# Control.net
KiCad netlist of a schematic drawn in Altium Designer
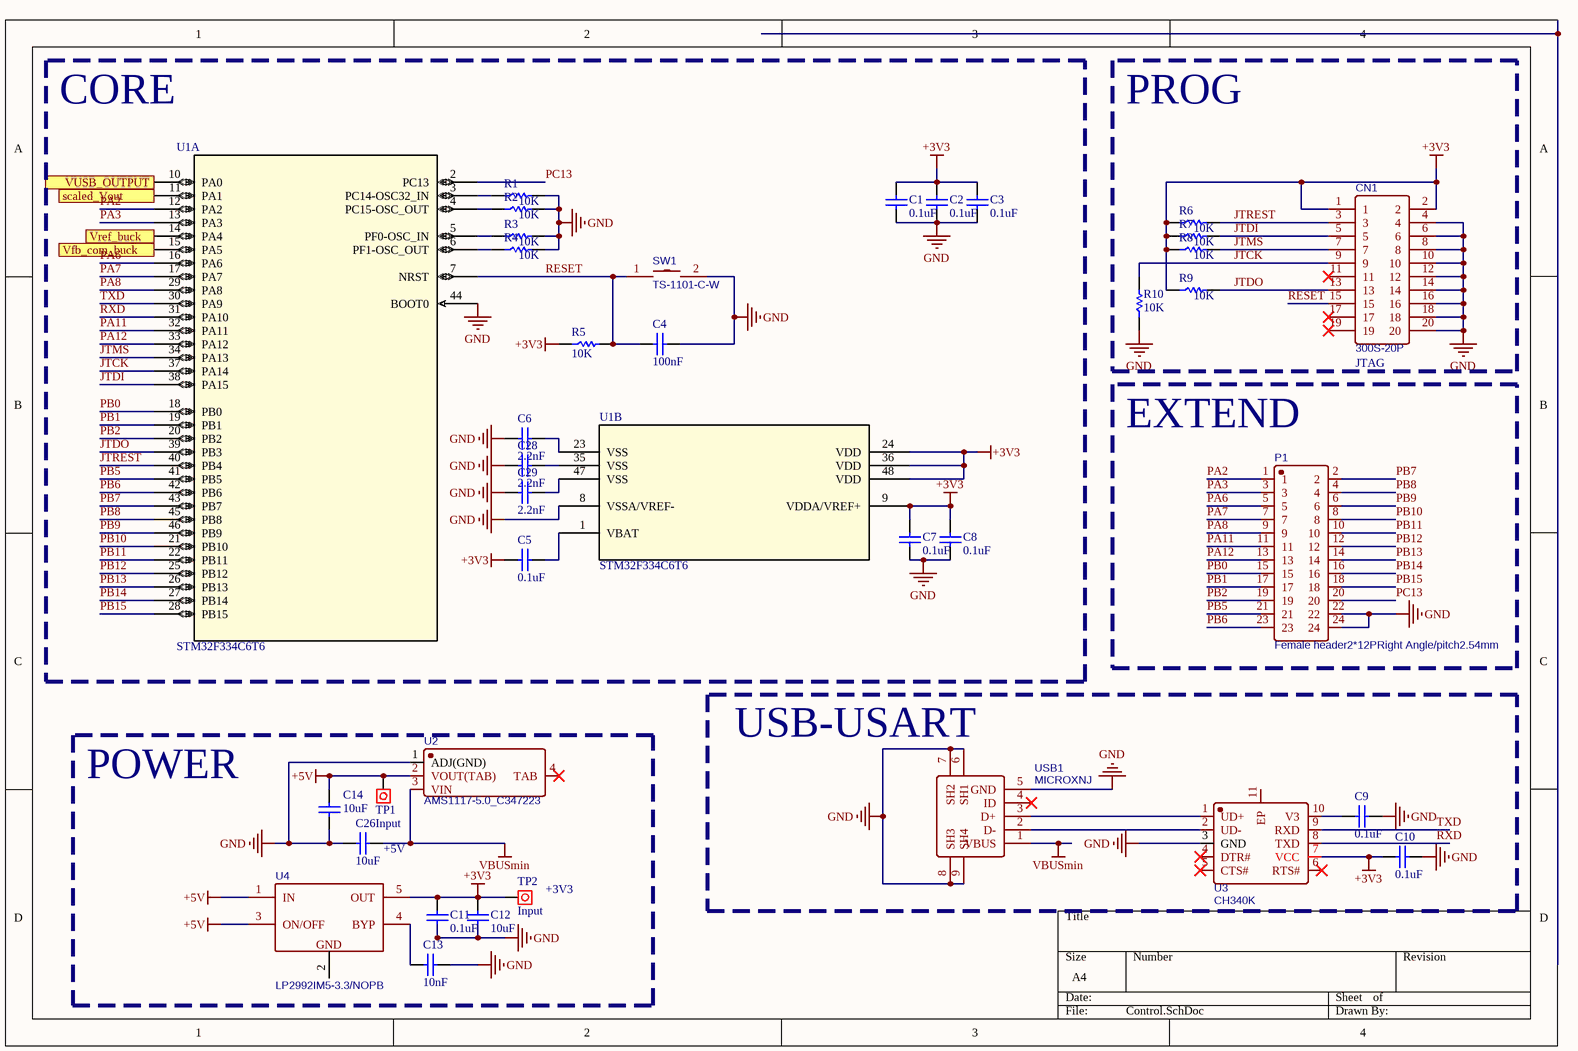
[diagram p0: Control.SchDoc]

(export (version "E")
  (design (tool "Eeschema 10.0.6"))
  (components
    (comp (ref "C1")
      (value "0.1uF")
      (footprint "0805C")
      (description "Capacitor")
      (fields (field (name "REVIEWED BY") "RM - 2018/08/05"))
      (libsource (lib "Portable power supply") (part "C_0.1uf"))
    )
    (comp (ref "C2")
      (value "0.1uF")
      (footprint "0805C")
      (description "Capacitor")
      (fields (field (name "REVIEWED BY") "RM - 2018/08/05"))
      (libsource (lib "Portable power supply") (part "C_0.1uf"))
    )
    (comp (ref "C3")
      (value "0.1uF")
      (footprint "0805C")
      (description "Capacitor")
      (fields (field (name "REVIEWED BY") "RM - 2018/08/05"))
      (libsource (lib "Portable power supply") (part "C_0.1uf"))
    )
    (comp (ref "C4")
      (value "100nF")
      (footprint "0805C")
      (description "Capacitor")
      (fields (field (name "REVIEWED BY") "RM - 2018/08/05"))
      (libsource (lib "Portable power supply") (part "C_100nf"))
    )
    (comp (ref "C5")
      (value "0.1uF")
      (footprint "0805C")
      (description "Capacitor")
      (fields (field (name "REVIEWED BY") "RM - 2018/08/05"))
      (libsource (lib "Portable power supply") (part "C_0.1uf"))
    )
    (comp (ref "C6")
      (value "2.2nF")
      (footprint "0805C")
      (description "Capacitor")
      (fields (field (name "REVIEWED BY") "RM - 2018/08/05"))
      (libsource (lib "Portable power supply") (part "C_2.2nF"))
    )
    (comp (ref "C7")
      (value "0.1uF")
      (footprint "0805C")
      (description "Capacitor")
      (fields (field (name "REVIEWED BY") "RM - 2018/08/05"))
      (libsource (lib "Portable power supply") (part "C_0.1uf"))
    )
    (comp (ref "C8")
      (value "0.1uF")
      (footprint "0805C")
      (description "Capacitor")
      (fields (field (name "REVIEWED BY") "RM - 2018/08/05"))
      (libsource (lib "Portable power supply") (part "C_0.1uf"))
    )
    (comp (ref "C9")
      (value "0.1uF")
      (footprint "0805C")
      (description "Capacitor")
      (fields (field (name "REVIEWED BY") "RM - 2018/08/05"))
      (libsource (lib "Portable power supply") (part "C_0.1uf"))
    )
    (comp (ref "C10")
      (value "0.1uF")
      (footprint "0805C")
      (description "Capacitor")
      (fields (field (name "REVIEWED BY") "RM - 2018/08/05"))
      (libsource (lib "Portable power supply") (part "C_0.1uf"))
    )
    (comp (ref "C11")
      (value "0.1uF")
      (footprint "0805C")
      (description "Capacitor")
      (fields (field (name "REVIEWED BY") "RM - 2018/08/05"))
      (libsource (lib "Portable power supply") (part "C_0.1uf"))
    )
    (comp (ref "C12")
      (value "10uF")
      (footprint "0805C")
      (description "Capacitor")
      (fields (field (name "REVIEWED BY") "RM - 2018/08/05"))
      (libsource (lib "Portable power supply") (part "C_10uf"))
    )
    (comp (ref "C13")
      (value "10nF")
      (footprint "0805C")
      (description "Capacitor")
      (fields (field (name "REVIEWED BY") "RM - 2018/08/05"))
      (libsource (lib "Portable power supply") (part "C_10nF"))
    )
    (comp (ref "C14")
      (value "10uF")
      (footprint "0805C")
      (description "Capacitor")
      (fields (field (name "REVIEWED BY") "RM - 2018/08/05"))
      (libsource (lib "Portable power supply") (part "C_10uf"))
    )
    (comp (ref "C26")
      (value "10uF")
      (footprint "0805C")
      (description "Capacitor")
      (fields (field (name "REVIEWED BY") "RM - 2018/08/05"))
      (libsource (lib "Portable power supply") (part "C_10uf"))
    )
    (comp (ref "C28")
      (value "2.2nF")
      (footprint "0805C")
      (description "Capacitor")
      (fields (field (name "REVIEWED BY") "RM - 2018/08/05"))
      (libsource (lib "Portable power supply") (part "C_2.2nF"))
    )
    (comp (ref "C29")
      (value "2.2nF")
      (footprint "0805C")
      (description "Capacitor")
      (fields (field (name "REVIEWED BY") "RM - 2018/08/05"))
      (libsource (lib "Portable power supply") (part "C_2.2nF"))
    )
    (comp (ref "CN1")
      (value "300S-20P")
      (footprint "CONN-TH_300S-20P")
      (fields (field (name "BOM_SUPPLIER PART") "C132442") (field (name "CONTRIBUTOR") "LCSC"))
      (libsource (lib "Portable power supply") (part "300S-20P"))
    )
    (comp (ref "P1")
      (value "Female header2*12PRight Angle/pitch2.54mm")
      (footprint "HDR-TH_24P-P2.54-V-F-R2-C12-S2.54")
      (fields (field (name "BOM_SUPPLIER PART") "C62744"))
      (libsource (lib "Portable power supply") (part "Female header2*12PRight Angle/pitch2.54mm"))
    )
    (comp (ref "R1")
      (value "10K")
      (footprint "0805")
      (description "Resistor")
      (fields (field (name "REVIEWED BY") "RM - 2018/08/05"))
      (libsource (lib "Portable power supply") (part "R_10k"))
    )
    (comp (ref "R2")
      (value "10K")
      (footprint "0805")
      (description "Resistor")
      (fields (field (name "REVIEWED BY") "RM - 2018/08/05"))
      (libsource (lib "Portable power supply") (part "R_10k"))
    )
    (comp (ref "R3")
      (value "10K")
      (footprint "0805")
      (description "Resistor")
      (fields (field (name "REVIEWED BY") "RM - 2018/08/05"))
      (libsource (lib "Portable power supply") (part "R_10k"))
    )
    (comp (ref "R4")
      (value "10K")
      (footprint "0805")
      (description "Resistor")
      (fields (field (name "REVIEWED BY") "RM - 2018/08/05"))
      (libsource (lib "Portable power supply") (part "R_10k"))
    )
    (comp (ref "R5")
      (value "10K")
      (footprint "0805")
      (description "Resistor")
      (fields (field (name "REVIEWED BY") "RM - 2018/08/05"))
      (libsource (lib "Portable power supply") (part "R_10k"))
    )
    (comp (ref "R6")
      (value "10K")
      (footprint "0805")
      (description "Resistor")
      (fields (field (name "REVIEWED BY") "RM - 2018/08/05"))
      (libsource (lib "Portable power supply") (part "R_10k"))
    )
    (comp (ref "R7")
      (value "10K")
      (footprint "0805")
      (description "Resistor")
      (fields (field (name "REVIEWED BY") "RM - 2018/08/05"))
      (libsource (lib "Portable power supply") (part "R_10k"))
    )
    (comp (ref "R8")
      (value "10K")
      (footprint "0805")
      (description "Resistor")
      (fields (field (name "REVIEWED BY") "RM - 2018/08/05"))
      (libsource (lib "Portable power supply") (part "R_10k"))
    )
    (comp (ref "R9")
      (value "10K")
      (footprint "0805")
      (description "Resistor")
      (fields (field (name "REVIEWED BY") "RM - 2018/08/05"))
      (libsource (lib "Portable power supply") (part "R_10k"))
    )
    (comp (ref "R10")
      (value "10K")
      (footprint "0805")
      (description "Resistor")
      (fields (field (name "REVIEWED BY") "RM - 2018/08/05"))
      (libsource (lib "Portable power supply") (part "R_10k"))
    )
    (comp (ref "SW1")
      (value "TS-1101-C-W")
      (footprint "SW-SMD_L6.0-W3.3-LS8.0")
      (fields (field (name "BOM_SUPPLIER PART") "C318938") (field (name "CONTRIBUTOR") "LCSC"))
      (libsource (lib "Portable power supply") (part "TS-1101-C-W"))
    )
    (comp (ref "TP1")
      (value "Input")
      (footprint "Testpoin")
      (description "Pad")
      (fields (field (name "Comment") "INPUT"))
      (libsource (lib "Portable power supply") (part "Test Point"))
    )
    (comp (ref "TP2")
      (value "Input")
      (footprint "Testpoin")
      (description "Pad")
      (fields (field (name "Comment") "INPUT"))
      (libsource (lib "Portable power supply") (part "Test Point"))
    )
    (comp (ref "U1")
      (value "STM32F334C6T6")
      (footprint "LQFP48-7x7mm")
      (description "No Description Available")
      (fields (field (name "COPYRIGHT") "Copyright (C) 2021 Ultra Librarian. All rights reserved."))
      (libsource (lib "Portable power supply") (part "STM32F334C6T6"))
    )
    (comp (ref "U2")
      (value "AMS1117-5.0_C347223")
      (footprint "SOT-223_L6.7-W3.5-P2.30-BR")
      (fields
        (field (name "BOM_SUPPLIER PART") "C347223")
        (field (name "BOM_MANUFACTURER PART") "AMS1117-5.0")
        (field (name "CONTRIBUTOR") "LCSC")
      )
      (libsource (lib "Portable power supply") (part "AMS1117-5.0_C347223"))
    )
    (comp (ref "U3")
      (value "CH340K")
      (footprint "ESOP-10_L4.9-W3.9-P1.00-LS6.2-BL-EP")
      (fields (field (name "BOM_SUPPLIER PART") "C968586") (field (name "CONTRIBUTOR") "LCSC"))
      (libsource (lib "Portable power supply") (part "CH340K"))
    )
    (comp (ref "U4")
      (value "LP2992IM5-3.3/NOPB")
      (footprint "SOT-23-5_L3.0-W1.7-P0.95-LS2.8-BR")
      (fields (field (name "BOM_SUPPLIER PART") "C129353") (field (name "CONTRIBUTOR") "LCSC"))
      (libsource (lib "Portable power supply") (part "LP2992IM5-3.3/NOPB"))
    )
    (comp (ref "USB1")
      (value "MICROXNJ")
      (footprint "MICRO-USB-SMD_MICROXNJ")
      (fields
        (field (name "BOM_SUPPLIER PART") "C404969")
        (field (name "BOM_MANUFACTURER PART") "MicroXNJ")
        (field (name "CONTRIBUTOR") "LCSC")
      )
      (libsource (lib "Portable power supply") (part "MICROXNJ"))
    )
  )
  (nets
    (net (code "1") (name "+3V3") (class "Default")
      (node (ref "C1") (pin "1") (pinfunction "1_1") (pintype "passive"))
      (node (ref "C10") (pin "2") (pinfunction "2_2") (pintype "passive"))
      (node (ref "C11") (pin "1") (pinfunction "1_1") (pintype "passive"))
      (node (ref "C12") (pin "1") (pinfunction "1_1") (pintype "passive"))
      (node (ref "C2") (pin "1") (pinfunction "1_1") (pintype "passive"))
      (node (ref "C3") (pin "1") (pinfunction "1_1") (pintype "passive"))
      (node (ref "C5") (pin "2") (pinfunction "2_2") (pintype "passive"))
      (node (ref "C7") (pin "1") (pinfunction "1_1") (pintype "passive"))
      (node (ref "C8") (pin "1") (pinfunction "1_1") (pintype "passive"))
      (node (ref "CN1") (pin "1") (pinfunction "1_1") (pintype "passive"))
      (node (ref "CN1") (pin "2") (pinfunction "2_2") (pintype "passive"))
      (node (ref "R5") (pin "1") (pintype "passive"))
      (node (ref "R6") (pin "1") (pintype "passive"))
      (node (ref "R7") (pin "1") (pintype "passive"))
      (node (ref "R8") (pin "1") (pintype "passive"))
      (node (ref "R9") (pin "1") (pintype "passive"))
      (node (ref "TP2") (pin "1") (pintype "passive"))
      (node (ref "U1") (pin "24") (pinfunction "VDD_24") (pintype "power_in"))
      (node (ref "U1") (pin "36") (pinfunction "VDD_36") (pintype "power_in"))
      (node (ref "U1") (pin "48") (pinfunction "VDD_48") (pintype "power_in"))
      (node (ref "U1") (pin "9") (pinfunction "VDDA/VREF+_9") (pintype "power_in"))
      (node (ref "U3") (pin "7") (pinfunction "VCC_7") (pintype "passive"))
      (node (ref "U4") (pin "5") (pinfunction "OUT_5") (pintype "passive"))
    )
    (net (code "2") (name "+5V") (class "Default")
      (node (ref "C14") (pin "1") (pinfunction "1_1") (pintype "passive"))
      (node (ref "TP1") (pin "1") (pintype "passive"))
      (node (ref "U2") (pin "2") (pinfunction "VOUT(TAB)_2") (pintype "passive"))
      (node (ref "U4") (pin "1") (pinfunction "IN_1") (pintype "passive"))
      (node (ref "U4") (pin "3") (pinfunction "ON/OFF_3") (pintype "passive"))
    )
    (net (code "3") (name "/JTCK") (class "Default")
      (node (ref "CN1") (pin "9") (pinfunction "9_9") (pintype "passive"))
      (node (ref "R10") (pin "2") (pintype "passive"))
      (node (ref "U1") (pin "37") (pinfunction "PA14_37") (pintype "bidirectional"))
    )
    (net (code "4") (name "/JTDI") (class "Default")
      (node (ref "CN1") (pin "5") (pinfunction "5_5") (pintype "passive"))
      (node (ref "R7") (pin "2") (pintype "passive"))
      (node (ref "U1") (pin "38") (pinfunction "PA15_38") (pintype "bidirectional"))
    )
    (net (code "5") (name "/JTDO") (class "Default")
      (node (ref "CN1") (pin "13") (pinfunction "13_13") (pintype "passive"))
      (node (ref "R9") (pin "2") (pintype "passive"))
      (node (ref "U1") (pin "39") (pinfunction "PB3_39") (pintype "bidirectional"))
    )
    (net (code "6") (name "/JTMS") (class "Default")
      (node (ref "CN1") (pin "7") (pinfunction "7_7") (pintype "passive"))
      (node (ref "R8") (pin "2") (pintype "passive"))
      (node (ref "U1") (pin "34") (pinfunction "PA13_34") (pintype "bidirectional"))
    )
    (net (code "7") (name "/JTREST") (class "Default")
      (node (ref "CN1") (pin "3") (pinfunction "3_3") (pintype "passive"))
      (node (ref "R6") (pin "2") (pintype "passive"))
      (node (ref "U1") (pin "40") (pinfunction "PB4_40") (pintype "bidirectional"))
    )
    (net (code "8") (name "/PA2") (class "Default")
      (node (ref "P1") (pin "1") (pinfunction "1_1") (pintype "passive"))
      (node (ref "U1") (pin "12") (pinfunction "PA2_12") (pintype "bidirectional"))
    )
    (net (code "9") (name "/PA3") (class "Default")
      (node (ref "P1") (pin "3") (pinfunction "3_3") (pintype "passive"))
      (node (ref "U1") (pin "13") (pinfunction "PA3_13") (pintype "bidirectional"))
    )
    (net (code "10") (name "/PA6") (class "Default")
      (node (ref "P1") (pin "5") (pinfunction "5_5") (pintype "passive"))
      (node (ref "U1") (pin "16") (pinfunction "PA6_16") (pintype "bidirectional"))
    )
    (net (code "11") (name "/PA7") (class "Default")
      (node (ref "P1") (pin "7") (pinfunction "7_7") (pintype "passive"))
      (node (ref "U1") (pin "17") (pinfunction "PA7_17") (pintype "bidirectional"))
    )
    (net (code "12") (name "/PA8") (class "Default")
      (node (ref "P1") (pin "9") (pinfunction "9_9") (pintype "passive"))
      (node (ref "U1") (pin "29") (pinfunction "PA8_29") (pintype "bidirectional"))
    )
    (net (code "13") (name "/PA11") (class "Default")
      (node (ref "P1") (pin "11") (pinfunction "11_11") (pintype "passive"))
      (node (ref "U1") (pin "32") (pinfunction "PA11_32") (pintype "bidirectional"))
    )
    (net (code "14") (name "/PA12") (class "Default")
      (node (ref "P1") (pin "13") (pinfunction "13_13") (pintype "passive"))
      (node (ref "U1") (pin "33") (pinfunction "PA12_33") (pintype "bidirectional"))
    )
    (net (code "15") (name "/PB0") (class "Default")
      (node (ref "P1") (pin "15") (pinfunction "15_15") (pintype "passive"))
      (node (ref "U1") (pin "18") (pinfunction "PB0_18") (pintype "bidirectional"))
    )
    (net (code "16") (name "/PB1") (class "Default")
      (node (ref "P1") (pin "17") (pinfunction "17_17") (pintype "passive"))
      (node (ref "U1") (pin "19") (pinfunction "PB1_19") (pintype "bidirectional"))
    )
    (net (code "17") (name "/PB2") (class "Default")
      (node (ref "P1") (pin "19") (pinfunction "19_19") (pintype "passive"))
      (node (ref "U1") (pin "20") (pinfunction "PB2_20") (pintype "bidirectional"))
    )
    (net (code "18") (name "/PB5") (class "Default")
      (node (ref "P1") (pin "21") (pinfunction "21_21") (pintype "passive"))
      (node (ref "U1") (pin "41") (pinfunction "PB5_41") (pintype "bidirectional"))
    )
    (net (code "19") (name "/PB6") (class "Default")
      (node (ref "P1") (pin "23") (pinfunction "23_23") (pintype "passive"))
      (node (ref "U1") (pin "42") (pinfunction "PB6_42") (pintype "bidirectional"))
    )
    (net (code "20") (name "/PB7") (class "Default")
      (node (ref "P1") (pin "2") (pinfunction "2_2") (pintype "passive"))
      (node (ref "U1") (pin "43") (pinfunction "PB7_43") (pintype "bidirectional"))
    )
    (net (code "21") (name "/PB8") (class "Default")
      (node (ref "P1") (pin "4") (pinfunction "4_4") (pintype "passive"))
      (node (ref "U1") (pin "45") (pinfunction "PB8_45") (pintype "bidirectional"))
    )
    (net (code "22") (name "/PB9") (class "Default")
      (node (ref "P1") (pin "6") (pinfunction "6_6") (pintype "passive"))
      (node (ref "U1") (pin "46") (pinfunction "PB9_46") (pintype "bidirectional"))
    )
    (net (code "23") (name "/PB10") (class "Default")
      (node (ref "P1") (pin "8") (pinfunction "8_8") (pintype "passive"))
      (node (ref "U1") (pin "21") (pinfunction "PB10_21") (pintype "bidirectional"))
    )
    (net (code "24") (name "/PB11") (class "Default")
      (node (ref "P1") (pin "10") (pinfunction "10_10") (pintype "passive"))
      (node (ref "U1") (pin "22") (pinfunction "PB11_22") (pintype "bidirectional"))
    )
    (net (code "25") (name "/PB12") (class "Default")
      (node (ref "P1") (pin "12") (pinfunction "12_12") (pintype "passive"))
      (node (ref "U1") (pin "25") (pinfunction "PB12_25") (pintype "bidirectional"))
    )
    (net (code "26") (name "/PB13") (class "Default")
      (node (ref "P1") (pin "14") (pinfunction "14_14") (pintype "passive"))
      (node (ref "U1") (pin "26") (pinfunction "PB13_26") (pintype "bidirectional"))
    )
    (net (code "27") (name "/PB14") (class "Default")
      (node (ref "P1") (pin "16") (pinfunction "16_16") (pintype "passive"))
      (node (ref "U1") (pin "27") (pinfunction "PB14_27") (pintype "bidirectional"))
    )
    (net (code "28") (name "/PB15") (class "Default")
      (node (ref "P1") (pin "18") (pinfunction "18_18") (pintype "passive"))
      (node (ref "U1") (pin "28") (pinfunction "PB15_28") (pintype "bidirectional"))
    )
    (net (code "29") (name "/PC13") (class "Default")
      (node (ref "P1") (pin "20") (pinfunction "20_20") (pintype "passive"))
      (node (ref "U1") (pin "2") (pinfunction "PC13_2") (pintype "bidirectional"))
    )
    (net (code "30") (name "/RESET") (class "Default")
      (node (ref "C4") (pin "2") (pinfunction "2_2") (pintype "passive"))
      (node (ref "CN1") (pin "15") (pinfunction "15_15") (pintype "passive"))
      (node (ref "R5") (pin "2") (pintype "passive"))
      (node (ref "SW1") (pin "1") (pinfunction "1_1") (pintype "passive"))
      (node (ref "U1") (pin "7") (pinfunction "NRST_7") (pintype "bidirectional"))
    )
    (net (code "31") (name "/RXD") (class "Default")
      (node (ref "U1") (pin "31") (pinfunction "PA10_31") (pintype "bidirectional"))
      (node (ref "U3") (pin "8") (pinfunction "TXD_8") (pintype "passive"))
    )
    (net (code "32") (name "/TXD") (class "Default")
      (node (ref "U1") (pin "30") (pinfunction "PA9_30") (pintype "bidirectional"))
      (node (ref "U3") (pin "9") (pinfunction "RXD_9") (pintype "passive"))
    )
    (net (code "33") (name "/VUSB_OUTPUT") (class "Default")
      (node (ref "U1") (pin "10") (pinfunction "PA0_10") (pintype "bidirectional"))
    )
    (net (code "34") (name "/Vfb_com_buck") (class "Default")
      (node (ref "U1") (pin "15") (pinfunction "PA5_15") (pintype "bidirectional"))
    )
    (net (code "35") (name "/Vref_buck") (class "Default")
      (node (ref "U1") (pin "14") (pinfunction "PA4_14") (pintype "bidirectional"))
    )
    (net (code "36") (name "/scaled_Vout") (class "Default")
      (node (ref "U1") (pin "11") (pinfunction "PA1_11") (pintype "bidirectional"))
    )
    (net (code "37") (name "GND") (class "Default")
      (node (ref "C1") (pin "2") (pinfunction "2_2") (pintype "passive"))
      (node (ref "C10") (pin "1") (pinfunction "1_1") (pintype "passive"))
      (node (ref "C11") (pin "2") (pinfunction "2_2") (pintype "passive"))
      (node (ref "C12") (pin "2") (pinfunction "2_2") (pintype "passive"))
      (node (ref "C13") (pin "1") (pinfunction "1_1") (pintype "passive"))
      (node (ref "C14") (pin "2") (pinfunction "2_2") (pintype "passive"))
      (node (ref "C2") (pin "2") (pinfunction "2_2") (pintype "passive"))
      (node (ref "C26") (pin "2") (pinfunction "2_2") (pintype "passive"))
      (node (ref "C28") (pin "2") (pinfunction "2_2") (pintype "passive"))
      (node (ref "C29") (pin "2") (pinfunction "2_2") (pintype "passive"))
      (node (ref "C3") (pin "2") (pinfunction "2_2") (pintype "passive"))
      (node (ref "C4") (pin "1") (pinfunction "1_1") (pintype "passive"))
      (node (ref "C6") (pin "2") (pinfunction "2_2") (pintype "passive"))
      (node (ref "C7") (pin "2") (pinfunction "2_2") (pintype "passive"))
      (node (ref "C8") (pin "2") (pinfunction "2_2") (pintype "passive"))
      (node (ref "C9") (pin "2") (pinfunction "2_2") (pintype "passive"))
      (node (ref "CN1") (pin "10") (pinfunction "10_10") (pintype "passive"))
      (node (ref "CN1") (pin "12") (pinfunction "12_12") (pintype "passive"))
      (node (ref "CN1") (pin "14") (pinfunction "14_14") (pintype "passive"))
      (node (ref "CN1") (pin "16") (pinfunction "16_16") (pintype "passive"))
      (node (ref "CN1") (pin "18") (pinfunction "18_18") (pintype "passive"))
      (node (ref "CN1") (pin "20") (pinfunction "20_20") (pintype "passive"))
      (node (ref "CN1") (pin "4") (pinfunction "4_4") (pintype "passive"))
      (node (ref "CN1") (pin "6") (pinfunction "6_6") (pintype "passive"))
      (node (ref "CN1") (pin "8") (pinfunction "8_8") (pintype "passive"))
      (node (ref "P1") (pin "22") (pinfunction "22_22") (pintype "passive"))
      (node (ref "P1") (pin "24") (pinfunction "24_24") (pintype "passive"))
      (node (ref "R1") (pin "2") (pintype "passive"))
      (node (ref "R10") (pin "1") (pintype "passive"))
      (node (ref "R2") (pin "2") (pintype "passive"))
      (node (ref "R3") (pin "2") (pintype "passive"))
      (node (ref "R4") (pin "2") (pintype "passive"))
      (node (ref "SW1") (pin "2") (pinfunction "2_2") (pintype "passive"))
      (node (ref "U1") (pin "44") (pinfunction "BOOT0_44") (pintype "input"))
      (node (ref "U1") (pin "8") (pinfunction "VSSA/VREF-_8") (pintype "power_in"))
      (node (ref "U2") (pin "1") (pinfunction "ADJ(GND)_1") (pintype "passive"))
      (node (ref "U3") (pin "3") (pinfunction "GND_3") (pintype "passive"))
      (node (ref "USB1") (pin "5") (pinfunction "GND_5") (pintype "passive"))
      (node (ref "USB1") (pin "6") (pinfunction "SH1_6") (pintype "passive"))
      (node (ref "USB1") (pin "7") (pinfunction "SH2_7") (pintype "passive"))
      (node (ref "USB1") (pin "8") (pinfunction "SH3_8") (pintype "passive"))
      (node (ref "USB1") (pin "9") (pinfunction "SH4_9") (pintype "passive"))
    )
    (net (code "38") (name "Net-(C6-Pad1)") (class "Default")
      (node (ref "C6") (pin "1") (pinfunction "1_1") (pintype "passive"))
      (node (ref "U1") (pin "23") (pinfunction "VSS_23") (pintype "power_in"))
    )
    (net (code "39") (name "Net-(C28-Pad1)") (class "Default")
      (node (ref "C28") (pin "1") (pinfunction "1_1") (pintype "passive"))
      (node (ref "U1") (pin "35") (pinfunction "VSS_35") (pintype "power_in"))
    )
    (net (code "40") (name "Net-(C29-Pad1)") (class "Default")
      (node (ref "C29") (pin "1") (pinfunction "1_1") (pintype "passive"))
      (node (ref "U1") (pin "47") (pinfunction "VSS_47") (pintype "power_in"))
    )
    (net (code "41") (name "Net-(U1A-PC14-OSC32_IN)") (class "Default")
      (node (ref "R1") (pin "1") (pintype "passive"))
      (node (ref "U1") (pin "3") (pinfunction "PC14-OSC32_IN_3") (pintype "bidirectional"))
    )
    (net (code "42") (name "Net-(U1A-PC15-OSC_OUT)") (class "Default")
      (node (ref "R2") (pin "1") (pintype "passive"))
      (node (ref "U1") (pin "4") (pinfunction "PC15-OSC_OUT_4") (pintype "bidirectional"))
    )
    (net (code "43") (name "Net-(U1A-PF0-OSC_IN)") (class "Default")
      (node (ref "R3") (pin "1") (pintype "passive"))
      (node (ref "U1") (pin "5") (pinfunction "PF0-OSC_IN_5") (pintype "bidirectional"))
    )
    (net (code "44") (name "Net-(U1A-PF1-OSC_OUT)") (class "Default")
      (node (ref "R4") (pin "1") (pintype "passive"))
      (node (ref "U1") (pin "6") (pinfunction "PF1-OSC_OUT_6") (pintype "bidirectional"))
    )
    (net (code "45") (name "Net-(U1B-VBAT)") (class "Default")
      (node (ref "C5") (pin "1") (pinfunction "1_1") (pintype "passive"))
      (node (ref "U1") (pin "1") (pinfunction "VBAT_1") (pintype "power_in"))
    )
    (net (code "46") (name "Net-(U3-UD+)") (class "Default")
      (node (ref "U3") (pin "1") (pinfunction "UD+_1") (pintype "passive"))
      (node (ref "USB1") (pin "3") (pinfunction "D+_3") (pintype "passive"))
    )
    (net (code "47") (name "Net-(U3-UD-)") (class "Default")
      (node (ref "U3") (pin "2") (pinfunction "UD-_2") (pintype "passive"))
      (node (ref "USB1") (pin "2") (pinfunction "D-_2") (pintype "passive"))
    )
    (net (code "48") (name "Net-(U3-V3)") (class "Default")
      (node (ref "C9") (pin "1") (pinfunction "1_1") (pintype "passive"))
      (node (ref "U3") (pin "10") (pinfunction "V3_10") (pintype "passive"))
    )
    (net (code "49") (name "Net-(U4-BYP)") (class "Default")
      (node (ref "C13") (pin "2") (pinfunction "2_2") (pintype "passive"))
      (node (ref "U4") (pin "4") (pinfunction "BYP_4") (pintype "passive"))
    )
    (net (code "50") (name "VBUSmin") (class "Default")
      (node (ref "C26") (pin "1") (pinfunction "1_1") (pintype "passive"))
      (node (ref "U2") (pin "3") (pinfunction "VIN_3") (pintype "passive"))
      (node (ref "USB1") (pin "1") (pinfunction "VBUS_1") (pintype "passive"))
    )
    (net (code "51") (name "unconnected-(CN1-Pad11)") (class "Default")
      (node (ref "CN1") (pin "11") (pinfunction "11_11") (pintype "passive+no_connect"))
    )
    (net (code "52") (name "unconnected-(CN1-Pad17)") (class "Default")
      (node (ref "CN1") (pin "17") (pinfunction "17_17") (pintype "passive+no_connect"))
    )
    (net (code "53") (name "unconnected-(CN1-Pad19)") (class "Default")
      (node (ref "CN1") (pin "19") (pinfunction "19_19") (pintype "passive+no_connect"))
    )
    (net (code "54") (name "unconnected-(U2-TAB-Pad4)") (class "Default")
      (node (ref "U2") (pin "4") (pinfunction "TAB_4") (pintype "passive+no_connect"))
    )
    (net (code "55") (name "unconnected-(U3-CTS#-Pad5)") (class "Default")
      (node (ref "U3") (pin "5") (pinfunction "CTS#_5") (pintype "passive+no_connect"))
    )
    (net (code "56") (name "unconnected-(U3-DTR#-Pad4)") (class "Default")
      (node (ref "U3") (pin "4") (pinfunction "DTR#_4") (pintype "passive+no_connect"))
    )
    (net (code "57") (name "unconnected-(U3-EP-Pad11)") (class "Default")
      (node (ref "U3") (pin "11") (pinfunction "EP_11") (pintype "passive"))
    )
    (net (code "58") (name "unconnected-(U3-RTS#-Pad6)") (class "Default")
      (node (ref "U3") (pin "6") (pinfunction "RTS#_6") (pintype "passive+no_connect"))
    )
    (net (code "59") (name "unconnected-(U4-GND-Pad2)") (class "Default")
      (node (ref "U4") (pin "2") (pinfunction "GND_2") (pintype "passive"))
    )
    (net (code "60") (name "unconnected-(USB1-ID-Pad4)") (class "Default")
      (node (ref "USB1") (pin "4") (pinfunction "ID_4") (pintype "passive+no_connect"))
    )
  )
)
